# psu.net
KiCad netlist of a schematic drawn in EAGLE
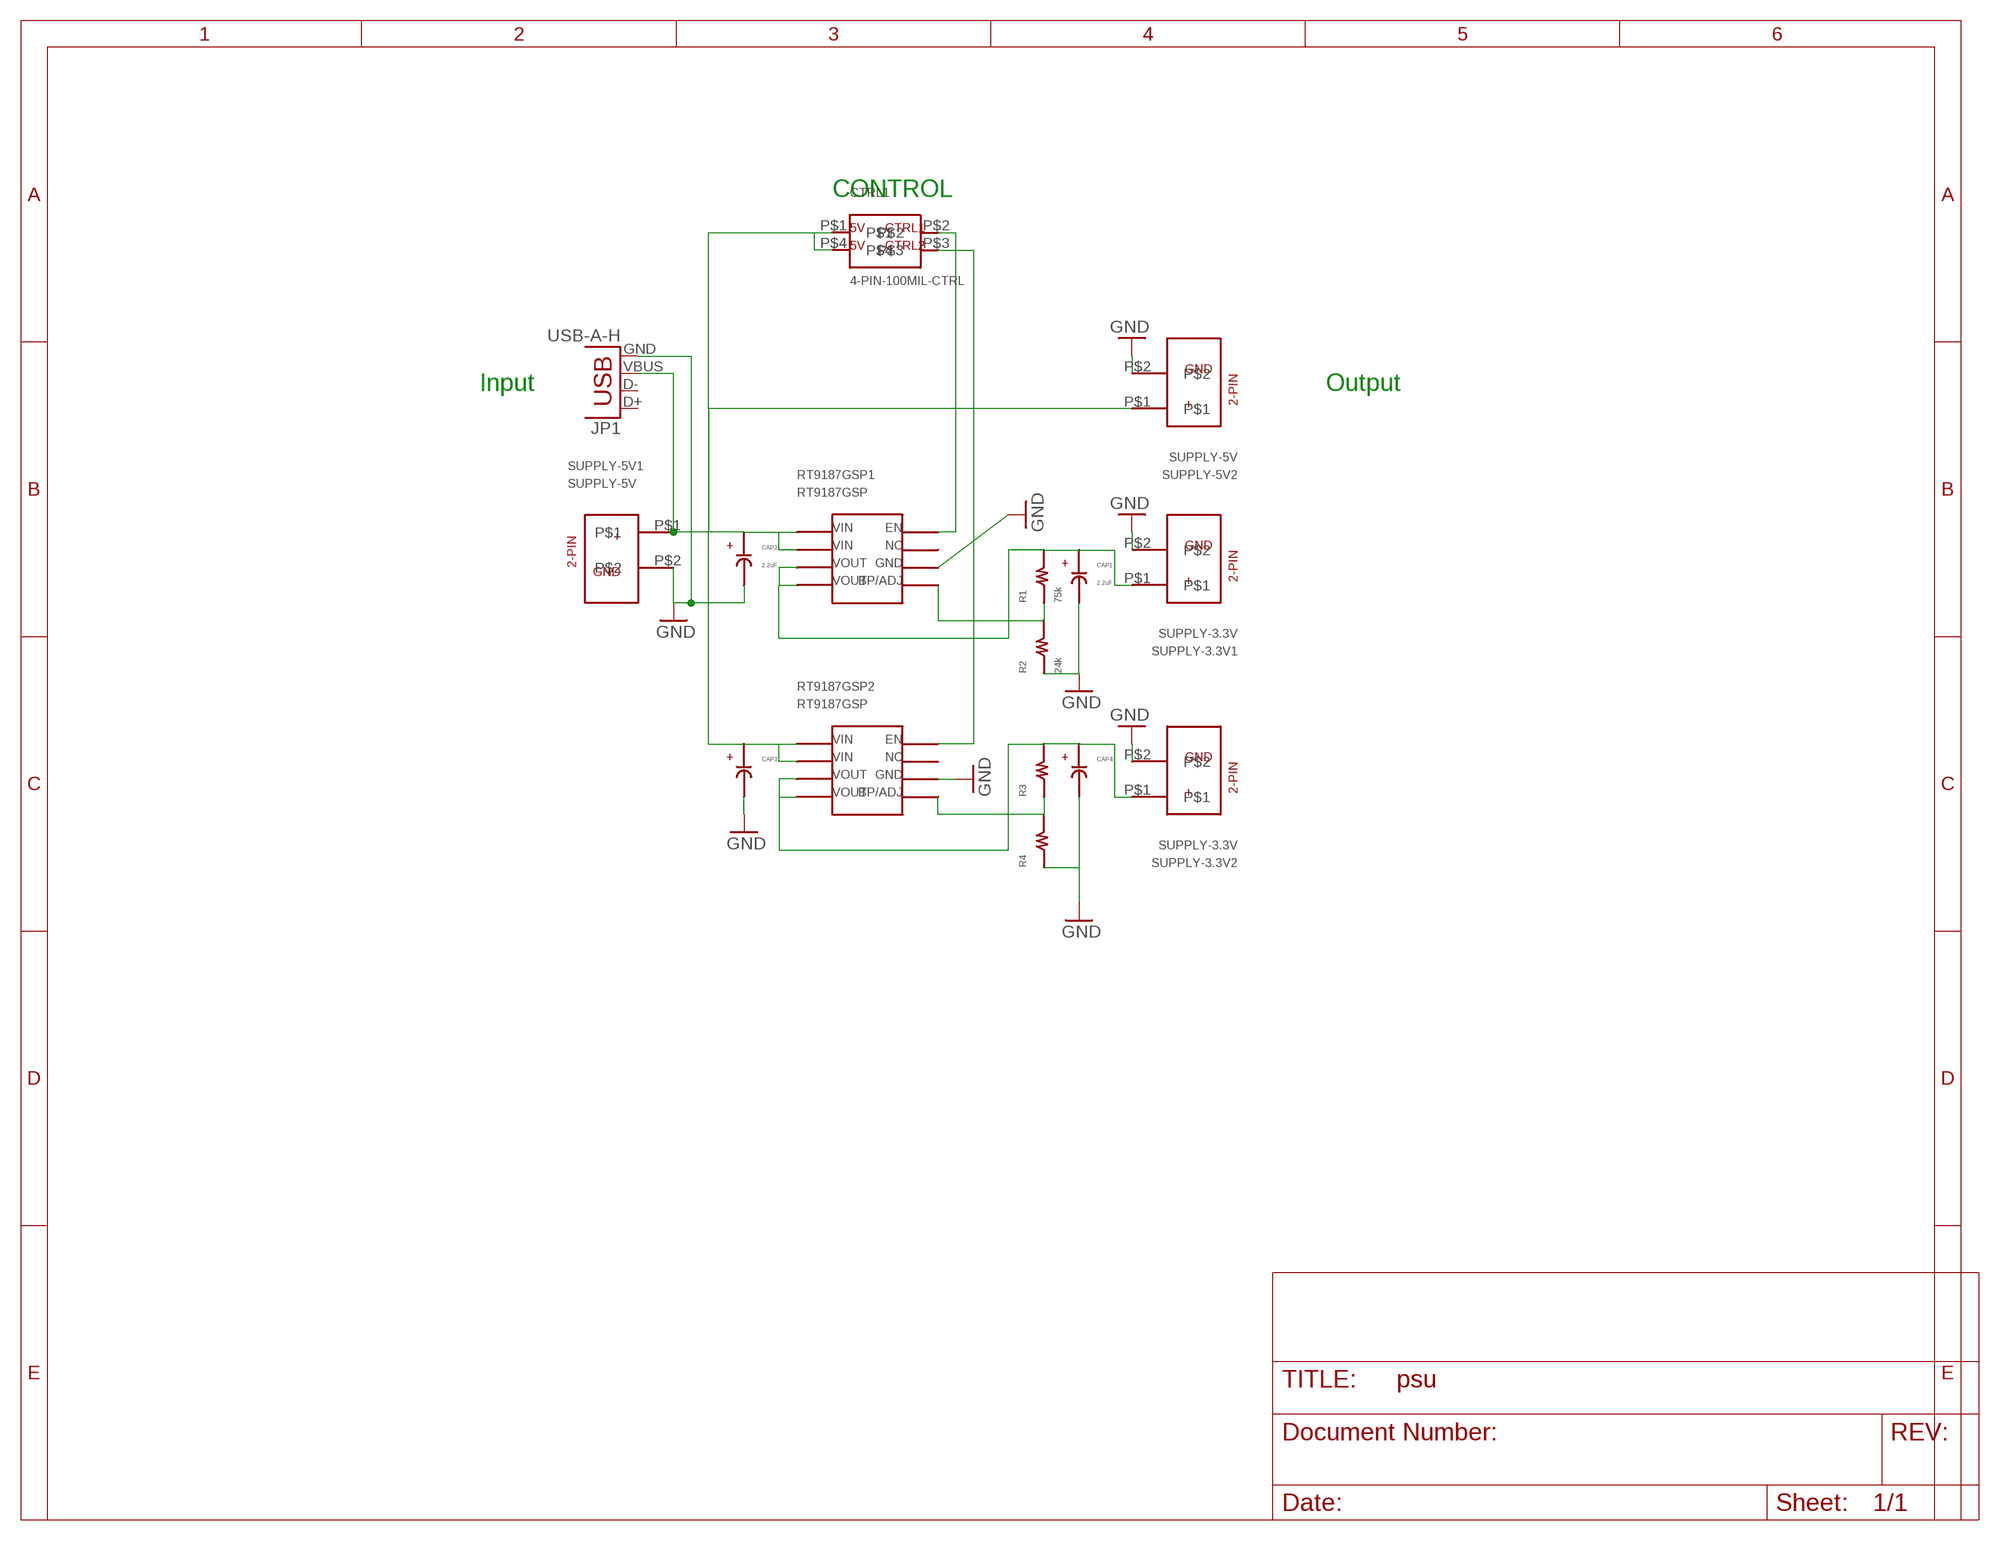
[diagram p0: schematic, sheet 1]

(export (version "E")
  (design (tool "Eeschema 10.0.6"))
  (components
    (comp (ref "CAP1")
      (value "2.2uF")
      (footprint "eagle-import:CAP-100MIL")
      (libsource (lib "eagle-import") (part "CAP-100MIL"))
    )
    (comp (ref "CAP2")
      (value "2.2uF")
      (footprint "eagle-import:CAP-100MIL")
      (libsource (lib "eagle-import") (part "CAP-100MIL"))
    )
    (comp (ref "CAP3")
      (value "CAP-100MIL")
      (footprint "eagle-import:CAP-100MIL")
      (libsource (lib "eagle-import") (part "CAP-100MIL"))
    )
    (comp (ref "CAP4")
      (value "CAP-100MIL")
      (footprint "eagle-import:CAP-100MIL")
      (libsource (lib "eagle-import") (part "CAP-100MIL"))
    )
    (comp (ref "CTRL1")
      (value "4-PIN-100MIL-CTRL")
      (footprint "eagle-import:4-PIN-100MIL-CTRL")
      (libsource (lib "eagle-import") (part "4-PIN-100MIL-CTRL"))
    )
    (comp (ref "JP1")
      (value "USB-A-H")
      (footprint "eagle-import:USB-A-H")
      (libsource (lib "eagle-import") (part "USB-A-H"))
    )
    (comp (ref "R1")
      (value "75k")
      (footprint "eagle-import:RESISTOR-SMD-1206")
      (libsource (lib "eagle-import") (part "RESISTOR-SMD-1206"))
    )
    (comp (ref "R2")
      (value "24k")
      (footprint "eagle-import:RESISTOR-SMD-1206")
      (libsource (lib "eagle-import") (part "RESISTOR-SMD-1206"))
    )
    (comp (ref "R3")
      (value "RESISTOR-SMD-1206")
      (footprint "eagle-import:RESISTOR-SMD-1206")
      (libsource (lib "eagle-import") (part "RESISTOR-SMD-1206"))
    )
    (comp (ref "R4")
      (value "RESISTOR-SMD-1206")
      (footprint "eagle-import:RESISTOR-SMD-1206")
      (libsource (lib "eagle-import") (part "RESISTOR-SMD-1206"))
    )
    (comp (ref "RT9187GSP1")
      (value "RT9187GSP")
      (footprint "eagle-import:SOP-8")
      (libsource (lib "eagle-import") (part "RT9187GSP"))
    )
    (comp (ref "RT9187GSP2")
      (value "RT9187GSP")
      (footprint "eagle-import:SOP-8")
      (libsource (lib "eagle-import") (part "RT9187GSP"))
    )
    (comp (ref "SUPPLY-3.3V1")
      (value "SUPPLY-3.3V")
      (footprint "eagle-import:2-PIN-100MIL-3.3V")
      (libsource (lib "eagle-import") (part "SUPPLY-3.3V"))
    )
    (comp (ref "SUPPLY-3.3V2")
      (value "SUPPLY-3.3V")
      (footprint "eagle-import:2-PIN-100MIL-3.3V")
      (libsource (lib "eagle-import") (part "SUPPLY-3.3V"))
    )
    (comp (ref "SUPPLY-5V1")
      (value "SUPPLY-5V")
      (footprint "eagle-import:2-PIN-100MIL-5V")
      (libsource (lib "eagle-import") (part "SUPPLY-5V"))
    )
    (comp (ref "SUPPLY-5V2")
      (value "SUPPLY-5V")
      (footprint "eagle-import:2-PIN-100MIL-5V")
      (libsource (lib "eagle-import") (part "SUPPLY-5V"))
    )
  )
  (nets
    (net (code "1") (name "GND") (class "Default")
      (node (ref "CAP1") (pin "P$2") (pinfunction "P$2_P$2") (pintype "bidirectional"))
      (node (ref "CAP2") (pin "P$2") (pinfunction "P$2_P$2") (pintype "bidirectional"))
      (node (ref "CAP3") (pin "P$2") (pinfunction "P$2_P$2") (pintype "bidirectional"))
      (node (ref "CAP4") (pin "P$2") (pinfunction "P$2_P$2") (pintype "bidirectional"))
      (node (ref "JP1") (pin "GND") (pinfunction "GND_GND") (pintype "bidirectional"))
      (node (ref "R2") (pin "P$1") (pinfunction "P$1_P$1") (pintype "bidirectional"))
      (node (ref "R4") (pin "P$1") (pinfunction "P$1_P$1") (pintype "bidirectional"))
      (node (ref "RT9187GSP1") (pin "P$6") (pinfunction "P$6_P$6") (pintype "bidirectional"))
      (node (ref "RT9187GSP2") (pin "P$6") (pinfunction "P$6_P$6") (pintype "bidirectional"))
      (node (ref "SUPPLY-3.3V1") (pin "P$2") (pinfunction "P$2_P$2") (pintype "bidirectional"))
      (node (ref "SUPPLY-3.3V2") (pin "P$2") (pinfunction "P$2_P$2") (pintype "bidirectional"))
      (node (ref "SUPPLY-5V1") (pin "P$2") (pinfunction "P$2_P$2") (pintype "bidirectional"))
      (node (ref "SUPPLY-5V2") (pin "P$2") (pinfunction "P$2_P$2") (pintype "bidirectional"))
    )
    (net (code "2") (name "Net-(CAP1-PadP$1)") (class "Default")
      (node (ref "CAP1") (pin "P$1") (pinfunction "P$1_P$1") (pintype "bidirectional"))
      (node (ref "R1") (pin "P$2") (pinfunction "P$2_P$2") (pintype "bidirectional"))
      (node (ref "RT9187GSP1") (pin "P$3") (pinfunction "P$3_P$3") (pintype "bidirectional"))
      (node (ref "RT9187GSP1") (pin "P$4") (pinfunction "P$4_P$4") (pintype "bidirectional"))
      (node (ref "SUPPLY-3.3V1") (pin "P$1") (pinfunction "P$1_P$1") (pintype "bidirectional"))
    )
    (net (code "3") (name "Net-(CAP2-PadP$1)") (class "Default")
      (node (ref "CAP2") (pin "P$1") (pinfunction "P$1_P$1") (pintype "bidirectional"))
      (node (ref "CAP3") (pin "P$1") (pinfunction "P$1_P$1") (pintype "bidirectional"))
      (node (ref "CTRL1") (pin "P$1") (pinfunction "P$1_P$1") (pintype "bidirectional"))
      (node (ref "CTRL1") (pin "P$4") (pinfunction "P$4_P$4") (pintype "bidirectional"))
      (node (ref "JP1") (pin "VBUS") (pinfunction "VBUS_VBUS") (pintype "bidirectional"))
      (node (ref "RT9187GSP1") (pin "P$1") (pinfunction "P$1_P$1") (pintype "bidirectional"))
      (node (ref "RT9187GSP1") (pin "P$2") (pinfunction "P$2_P$2") (pintype "bidirectional"))
      (node (ref "RT9187GSP2") (pin "P$1") (pinfunction "P$1_P$1") (pintype "bidirectional"))
      (node (ref "RT9187GSP2") (pin "P$2") (pinfunction "P$2_P$2") (pintype "bidirectional"))
      (node (ref "SUPPLY-5V1") (pin "P$1") (pinfunction "P$1_P$1") (pintype "bidirectional"))
      (node (ref "SUPPLY-5V2") (pin "P$1") (pinfunction "P$1_P$1") (pintype "bidirectional"))
    )
    (net (code "4") (name "Net-(CAP4-PadP$1)") (class "Default")
      (node (ref "CAP4") (pin "P$1") (pinfunction "P$1_P$1") (pintype "bidirectional"))
      (node (ref "R3") (pin "P$2") (pinfunction "P$2_P$2") (pintype "bidirectional"))
      (node (ref "RT9187GSP2") (pin "P$3") (pinfunction "P$3_P$3") (pintype "bidirectional"))
      (node (ref "RT9187GSP2") (pin "P$4") (pinfunction "P$4_P$4") (pintype "bidirectional"))
      (node (ref "SUPPLY-3.3V2") (pin "P$1") (pinfunction "P$1_P$1") (pintype "bidirectional"))
    )
    (net (code "5") (name "Net-(CTRL1-PadP$2)") (class "Default")
      (node (ref "CTRL1") (pin "P$2") (pinfunction "P$2_P$2") (pintype "bidirectional"))
      (node (ref "RT9187GSP1") (pin "P$8") (pinfunction "P$8_P$8") (pintype "bidirectional"))
    )
    (net (code "6") (name "Net-(CTRL1-PadP$3)") (class "Default")
      (node (ref "CTRL1") (pin "P$3") (pinfunction "P$3_P$3") (pintype "bidirectional"))
      (node (ref "RT9187GSP2") (pin "P$8") (pinfunction "P$8_P$8") (pintype "bidirectional"))
    )
    (net (code "7") (name "Net-(R1-PadP$1)") (class "Default")
      (node (ref "R1") (pin "P$1") (pinfunction "P$1_P$1") (pintype "bidirectional"))
      (node (ref "R2") (pin "P$2") (pinfunction "P$2_P$2") (pintype "bidirectional"))
      (node (ref "RT9187GSP1") (pin "P$5") (pinfunction "P$5_P$5") (pintype "bidirectional"))
    )
    (net (code "8") (name "Net-(R3-PadP$1)") (class "Default")
      (node (ref "R3") (pin "P$1") (pinfunction "P$1_P$1") (pintype "bidirectional"))
      (node (ref "R4") (pin "P$2") (pinfunction "P$2_P$2") (pintype "bidirectional"))
      (node (ref "RT9187GSP2") (pin "P$5") (pinfunction "P$5_P$5") (pintype "bidirectional"))
    )
    (net (code "9") (name "unconnected-(JP1-PadD+)") (class "Default")
      (node (ref "JP1") (pin "D+") (pinfunction "D+_D+") (pintype "bidirectional"))
    )
    (net (code "10") (name "unconnected-(JP1-PadD-)") (class "Default")
      (node (ref "JP1") (pin "D-") (pinfunction "D-_D-") (pintype "bidirectional"))
    )
    (net (code "11") (name "unconnected-(RT9187GSP1-PadP$7)") (class "Default")
      (node (ref "RT9187GSP1") (pin "P$7") (pinfunction "P$7_P$7") (pintype "bidirectional"))
    )
    (net (code "12") (name "unconnected-(RT9187GSP2-PadP$7)") (class "Default")
      (node (ref "RT9187GSP2") (pin "P$7") (pinfunction "P$7_P$7") (pintype "bidirectional"))
    )
  )
)
